# VOLTAGE_REGULATOR.net
KiCad netlist of a schematic drawn in Altium Designer
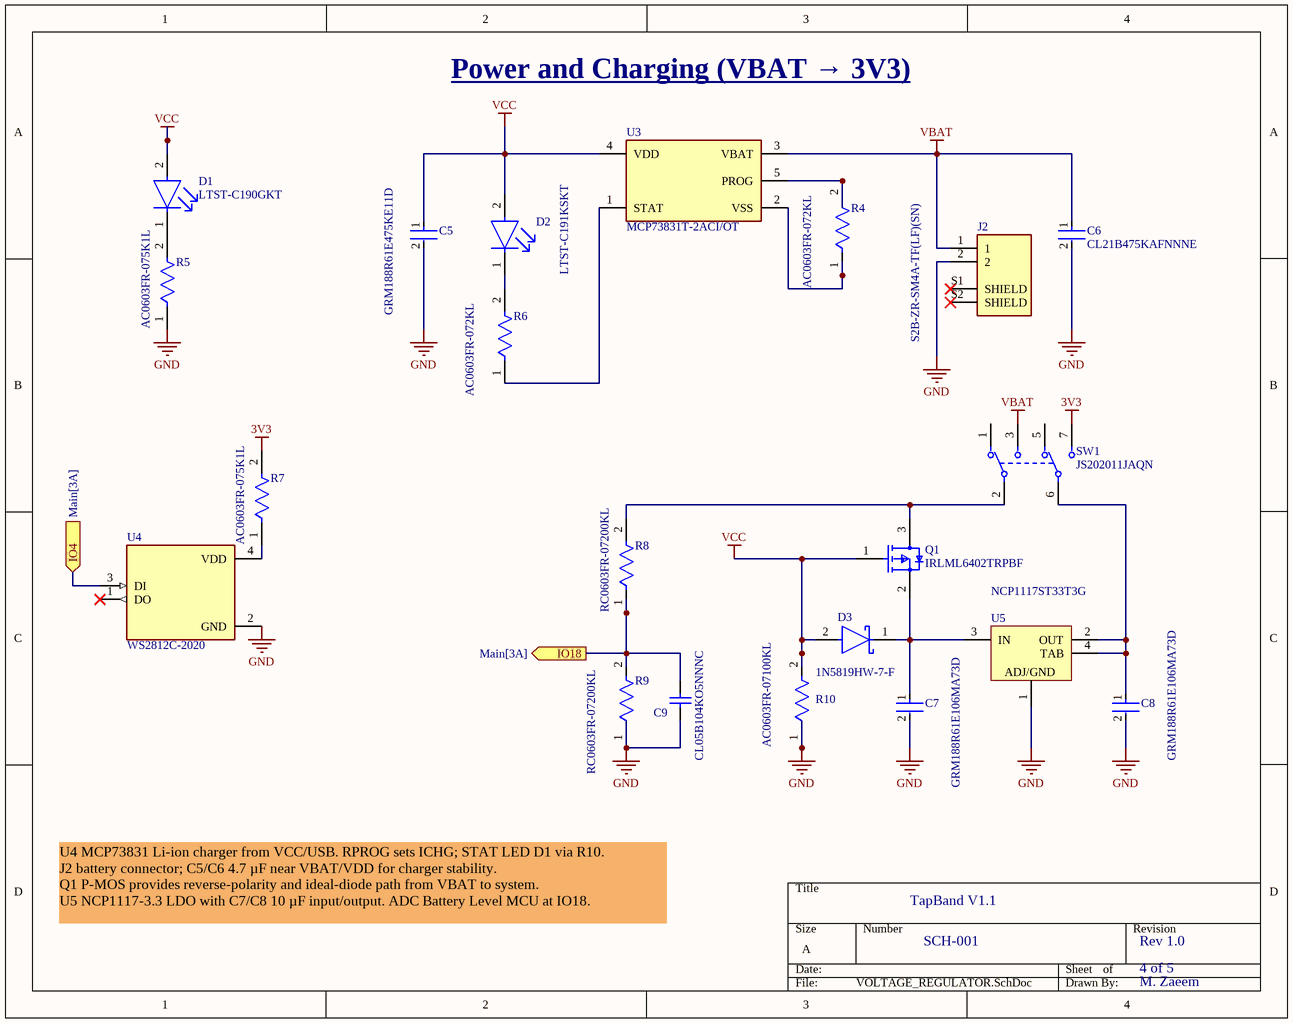
[diagram p0: VOLTAGE_REGULATOR.SchDoc]

(export (version "E")
  (design (tool "Eeschema 10.0.6"))
  (components
    (comp (ref "C5")
      (value "GRM188R61E475KE11D")
      (footprint "FP-GRM188-0_15-IPC_C")
      (description "Chip Multilayer Ceramic Capacitors for General Purpose, 0603, 4.7uF, X5R, 15%, 10%, 25V")
      (fields (field (name "VOLTAGE") "25V") (field (name "TOLERANCE") "10%"))
      (libsource (lib "Altium Content Vault") (part "02cd4be3c70576c341d710602a673aa"))
    )
    (comp (ref "C6")
      (value "CL21B475KAFNNNE")
      (footprint "FP-CL21-IPC_C")
      (description "CL21 Series 0805 4.7uF 25V ±10% Tolerance X7R Multilayer Ceramic Chip Capacitor")
      (fields (field (name "TOLERANCE") "10%"))
      (libsource (lib "Altium Content Vault") (part "b4654b650e69147ec39a6b967a45e02"))
    )
    (comp (ref "C7")
      (value "GRM188R61E106MA73D")
      (footprint "FP-GRM188-0_2-MFG")
      (description "Chip Multilayer Ceramic Capacitors for General Purpose, 0603, 10uF, X5R, 15%, 20%, 25V")
      (fields (field (name "TOLERANCE") "20%") (field (name "VOLTAGE") "25V"))
      (libsource (lib "Altium Content Vault") (part "11868f565c42a9108669ba33697ecf6"))
    )
    (comp (ref "C8")
      (value "GRM188R61E106MA73D")
      (footprint "FP-GRM188-0_2-MFG")
      (description "Chip Multilayer Ceramic Capacitors for General Purpose, 0603, 10uF, X5R, 15%, 20%, 25V")
      (fields (field (name "TOLERANCE") "20%") (field (name "VOLTAGE") "25V"))
      (libsource (lib "Altium Content Vault") (part "11868f565c42a9108669ba33697ecf6"))
    )
    (comp (ref "C9")
      (value "CL05B104KO5NNNC")
      (footprint "CAPC1050X55X23ML05T13")
      (description "Chip Capacitor, 100 nF, +/- 10%, 16 V, -55 to 125 degC, 0402 (1005 Metric), RoHS, Tape and Reel")
      (fields (field (name "MANUFACTURER") "Samsung Electro-Mechanics"))
      (libsource (lib "Altium Content Vault") (part "CAP-NP-2"))
    )
    (comp (ref "D1")
      (value "LTST-C190GKT")
      (footprint "FP-LTST-C190GKT-MFG")
      (description "LED GREEN CLEAR CHIP SMD")
      (fields (field (name "VOLTAGE") "2V"))
      (libsource (lib "Altium Content Vault") (part "8706943c75ba83719d021d2fdc84c58"))
    )
    (comp (ref "D2")
      (value "LTST-C191KSKT")
      (footprint "FP-LTST-C191KSKT-MFG")
      (description "LED YELLOW CLEAR SMD")
      (libsource (lib "Altium Content Vault") (part "8706943c75ba83719d021d2fdc84c58"))
    )
    (comp (ref "D3")
      (value "1N5819HW-7-F")
      (footprint "FP-SOD123-IPC_A")
      (description "DIODE SCHOTTKY 40V 1A SOD123")
      (libsource (lib "Altium Content Vault") (part "1d6ec82d83fb6aee721767c19dac4b9"))
    )
    (comp (ref "J2")
      (value "S2B-ZR-SM4A-TF(LF)(SN)")
      (footprint "JST_S2B-ZR-SM4A-TF(LF)(SN)")
      (description "Connector Header Surface Mount, Right Angle 2 position 0.059 (1.50mm)")
      (fields (field (name "MF") "JST Sales") (field (name "MP") "S2B-ZR-SM4A-TF (LF)(SN)"))
      (libsource (lib "S2B-ZR-SM4A-TF(LF)(SN)") (part "S2B-ZR-SM4A-TF(LF)(SN)"))
    )
    (comp (ref "Q1")
      (value "IRLML6402TRPBF")
      (footprint "FP-Micro3-MFG")
      (description "MOSFET P-CH 20V 3.7A SOT-23")
      (fields
        (field (name "OCTOPART") "https://octopart.com/irlml6402trpbf-infineon-65874989")
        (field (name "MANUFACTURER") "Infineon")
      )
      (libsource (lib "Altium Content Vault") (part "566027c8dc92b5207d53ac25ab3eb60"))
    )
    (comp (ref "R4")
      (value "AC0603FR-072KL")
      (footprint "FP-AC0603-IPC_B")
      (description "RES 2kΩ 1.00% 0.1W 0603")
      (fields (field (name "TOLERANCE") "1%"))
      (libsource (lib "Altium Content Vault") (part "1029c3af85768c4190bb7ad29bc67b5"))
    )
    (comp (ref "R5")
      (value "AC0603FR-075K1L")
      (footprint "FP-AC0603-MFG")
      (description "RES 5.1KΩ 1.00% 0.1W 0603")
      (fields (field (name "TOLERANCE") "1%"))
      (libsource (lib "Altium Content Vault") (part "1029c3af85768c4190bb7ad29bc67b5"))
    )
    (comp (ref "R6")
      (value "AC0603FR-072KL")
      (footprint "FP-AC0603-IPC_B")
      (description "RES 2kΩ 1.00% 0.1W 0603")
      (fields (field (name "TOLERANCE") "1%"))
      (libsource (lib "Altium Content Vault") (part "1029c3af85768c4190bb7ad29bc67b5"))
    )
    (comp (ref "R7")
      (value "AC0603FR-075K1L")
      (footprint "FP-AC0603-MFG")
      (description "RES 5.1KΩ 1.00% 0.1W 0603")
      (fields (field (name "TOLERANCE") "1%"))
      (libsource (lib "Altium Content Vault") (part "1029c3af85768c4190bb7ad29bc67b5"))
    )
    (comp (ref "R8")
      (value "RC0603FR-07200KL")
      (footprint "FP-RC0603-0_55-IPC_B")
      (description "RES SMD 200K OHM 1% 1/10W 0603")
      (fields (field (name "TOLERANCE") "1%"))
      (libsource (lib "Altium Content Vault") (part "1029c3af85768c4190bb7ad29bc67b5"))
    )
    (comp (ref "R9")
      (value "RC0603FR-07200KL")
      (footprint "FP-RC0603-0_55-IPC_B")
      (description "RES SMD 200K OHM 1% 1/10W 0603")
      (fields (field (name "TOLERANCE") "1%"))
      (libsource (lib "Altium Content Vault") (part "1029c3af85768c4190bb7ad29bc67b5"))
    )
    (comp (ref "R10")
      (value "AC0603FR-07100KL")
      (footprint "FP-AC0603-MFG")
      (description "RES 100KΩ 1.00% 0.1W 0603")
      (fields (field (name "TOLERANCE") "1%"))
      (libsource (lib "Altium Content Vault") (part "1029c3af85768c4190bb7ad29bc67b5"))
    )
    (comp (ref "SW1")
      (value "JS202011JAQN")
      (footprint "FP-JS202011JAQN-MFG")
      (description "SWITCH SLIDE DPDT 300MA 6V")
      (libsource (lib "Altium Content Vault") (part "66c5272d6436a01c7c428436b9d4858"))
    )
    (comp (ref "U3")
      (value "MCP73831T-2ACI/OT")
      (footprint "FP-C04-091-OT-MFG")
      (description "IC CONTROLLR LI-ION 4.2V SOT23-5")
      (libsource (lib "Altium Content Vault") (part "61f5a3bb3429d9e0caadea342aa3b19"))
    )
    (comp (ref "U4")
      (value "WS2812C-2020")
      (footprint "LED_WS2812C-2020")
      (description "Intelligent control LED integrated light source")
      (fields (field (name "MF") "Worldsemi"))
      (libsource (lib "WS2812C-2020") (part "WS2812C-2020"))
    )
    (comp (ref "U5")
      (value "NCP1117ST33T3G")
      (footprint "ONSC-SOT-223-4-318H-01_A_V")
      (fields (field (name "TOLERANCE") "1%"))
      (libsource (lib "Altium Content Vault") (part "ONSC-NCP1117-SOT223-4"))
    )
  )
  (nets
    (net (code "1") (name "/IO4") (class "Default")
      (node (ref "U4") (pin "3") (pinfunction "DI_3") (pintype "input"))
    )
    (net (code "2") (name "/IO18") (class "Default")
      (node (ref "C9") (pin "2") (pinfunction "2_2") (pintype "passive"))
      (node (ref "R8") (pin "1") (pinfunction "1_1") (pintype "passive"))
      (node (ref "R9") (pin "2") (pinfunction "2_2") (pintype "passive"))
    )
    (net (code "3") (name "3V3") (class "Default")
      (node (ref "R7") (pin "2") (pinfunction "2_2") (pintype "passive"))
      (node (ref "SW1") (pin "7") (pinfunction "7_7") (pintype "passive"))
    )
    (net (code "4") (name "GND") (class "Default")
      (node (ref "C5") (pin "2") (pinfunction "2_2") (pintype "passive"))
      (node (ref "C6") (pin "2") (pinfunction "2_2") (pintype "passive"))
      (node (ref "C7") (pin "2") (pinfunction "2_2") (pintype "passive"))
      (node (ref "C8") (pin "2") (pinfunction "2_2") (pintype "passive"))
      (node (ref "C9") (pin "1") (pinfunction "1_1") (pintype "passive"))
      (node (ref "J2") (pin "2") (pinfunction "2_2") (pintype "passive"))
      (node (ref "R10") (pin "1") (pinfunction "1_1") (pintype "passive"))
      (node (ref "R5") (pin "1") (pinfunction "1_1") (pintype "passive"))
      (node (ref "R9") (pin "1") (pinfunction "1_1") (pintype "passive"))
      (node (ref "U4") (pin "2") (pinfunction "GND_2") (pintype "power_in"))
      (node (ref "U5") (pin "1") (pinfunction "ADJ/GND_1") (pintype "passive"))
    )
    (net (code "5") (name "Net-(D1-C)") (class "Default")
      (node (ref "D1") (pin "1") (pinfunction "C_1") (pintype "passive"))
      (node (ref "R5") (pin "2") (pinfunction "2_2") (pintype "passive"))
    )
    (net (code "6") (name "Net-(D2-C)") (class "Default")
      (node (ref "D2") (pin "1") (pinfunction "C_1") (pintype "passive"))
      (node (ref "R6") (pin "2") (pinfunction "2_2") (pintype "passive"))
    )
    (net (code "7") (name "Net-(D3-C)") (class "Default")
      (node (ref "C7") (pin "1") (pinfunction "1_1") (pintype "passive"))
      (node (ref "D3") (pin "1") (pinfunction "C_1") (pintype "passive"))
      (node (ref "Q1") (pin "2") (pinfunction "S_2") (pintype "passive"))
      (node (ref "U5") (pin "3") (pinfunction "IN_3") (pintype "power_in"))
    )
    (net (code "8") (name "Net-(Q1-D)") (class "Default")
      (node (ref "Q1") (pin "3") (pinfunction "D_3") (pintype "passive"))
      (node (ref "R8") (pin "2") (pinfunction "2_2") (pintype "passive"))
      (node (ref "SW1") (pin "2") (pinfunction "1_C_2") (pintype "passive"))
    )
    (net (code "9") (name "Net-(SW1-2_C)") (class "Default")
      (node (ref "C8") (pin "1") (pinfunction "1_1") (pintype "passive"))
      (node (ref "SW1") (pin "6") (pinfunction "2_C_6") (pintype "passive"))
      (node (ref "U5") (pin "2") (pinfunction "OUT_2") (pintype "power_in"))
      (node (ref "U5") (pin "4") (pinfunction "TAB_4") (pintype "passive"))
    )
    (net (code "10") (name "Net-(U3-PROG)") (class "Default")
      (node (ref "R4") (pin "2") (pinfunction "2_2") (pintype "passive"))
      (node (ref "U3") (pin "5") (pinfunction "PROG_5") (pintype "passive"))
    )
    (net (code "11") (name "Net-(U3-STAT)") (class "Default")
      (node (ref "R6") (pin "1") (pinfunction "1_1") (pintype "passive"))
      (node (ref "U3") (pin "1") (pinfunction "STAT_1") (pintype "passive"))
    )
    (net (code "12") (name "Net-(U3-VSS)") (class "Default")
      (node (ref "R4") (pin "1") (pinfunction "1_1") (pintype "passive"))
      (node (ref "U3") (pin "2") (pinfunction "VSS_2") (pintype "power_in"))
    )
    (net (code "13") (name "Net-(U4-VDD)") (class "Default")
      (node (ref "R7") (pin "1") (pinfunction "1_1") (pintype "passive"))
      (node (ref "U4") (pin "4") (pinfunction "VDD_4") (pintype "power_in"))
    )
    (net (code "14") (name "VBAT") (class "Default")
      (node (ref "C6") (pin "1") (pinfunction "1_1") (pintype "passive"))
      (node (ref "J2") (pin "1") (pinfunction "1_1") (pintype "passive"))
      (node (ref "SW1") (pin "3") (pinfunction "3_3") (pintype "passive"))
      (node (ref "U3") (pin "3") (pinfunction "VBAT_3") (pintype "power_in"))
    )
    (net (code "15") (name "VCC") (class "Default")
      (node (ref "C5") (pin "1") (pinfunction "1_1") (pintype "passive"))
      (node (ref "D1") (pin "2") (pinfunction "A_2") (pintype "passive"))
      (node (ref "D2") (pin "2") (pinfunction "A_2") (pintype "passive"))
      (node (ref "D3") (pin "2") (pinfunction "A_2") (pintype "passive"))
      (node (ref "Q1") (pin "1") (pinfunction "G_1") (pintype "passive"))
      (node (ref "R10") (pin "2") (pinfunction "2_2") (pintype "passive"))
      (node (ref "U3") (pin "4") (pinfunction "VDD_4") (pintype "power_in"))
    )
    (net (code "16") (name "unconnected-(J2-SHIELD-PadS1)") (class "Default")
      (node (ref "J2") (pin "S1") (pinfunction "SHIELD_S1") (pintype "passive+no_connect"))
    )
    (net (code "17") (name "unconnected-(J2-SHIELD-PadS2)") (class "Default")
      (node (ref "J2") (pin "S2") (pinfunction "SHIELD_S2") (pintype "passive+no_connect"))
    )
    (net (code "18") (name "unconnected-(SW1-Pad1)") (class "Default")
      (node (ref "SW1") (pin "1") (pinfunction "1_1") (pintype "passive"))
    )
    (net (code "19") (name "unconnected-(SW1-Pad5)") (class "Default")
      (node (ref "SW1") (pin "5") (pinfunction "5_5") (pintype "passive"))
    )
    (net (code "20") (name "unconnected-(U4-DO-Pad1)") (class "Default")
      (node (ref "U4") (pin "1") (pinfunction "DO_1") (pintype "output+no_connect"))
    )
  )
)
